# mini_robot.net
KiCad netlist of a schematic drawn in EAGLE
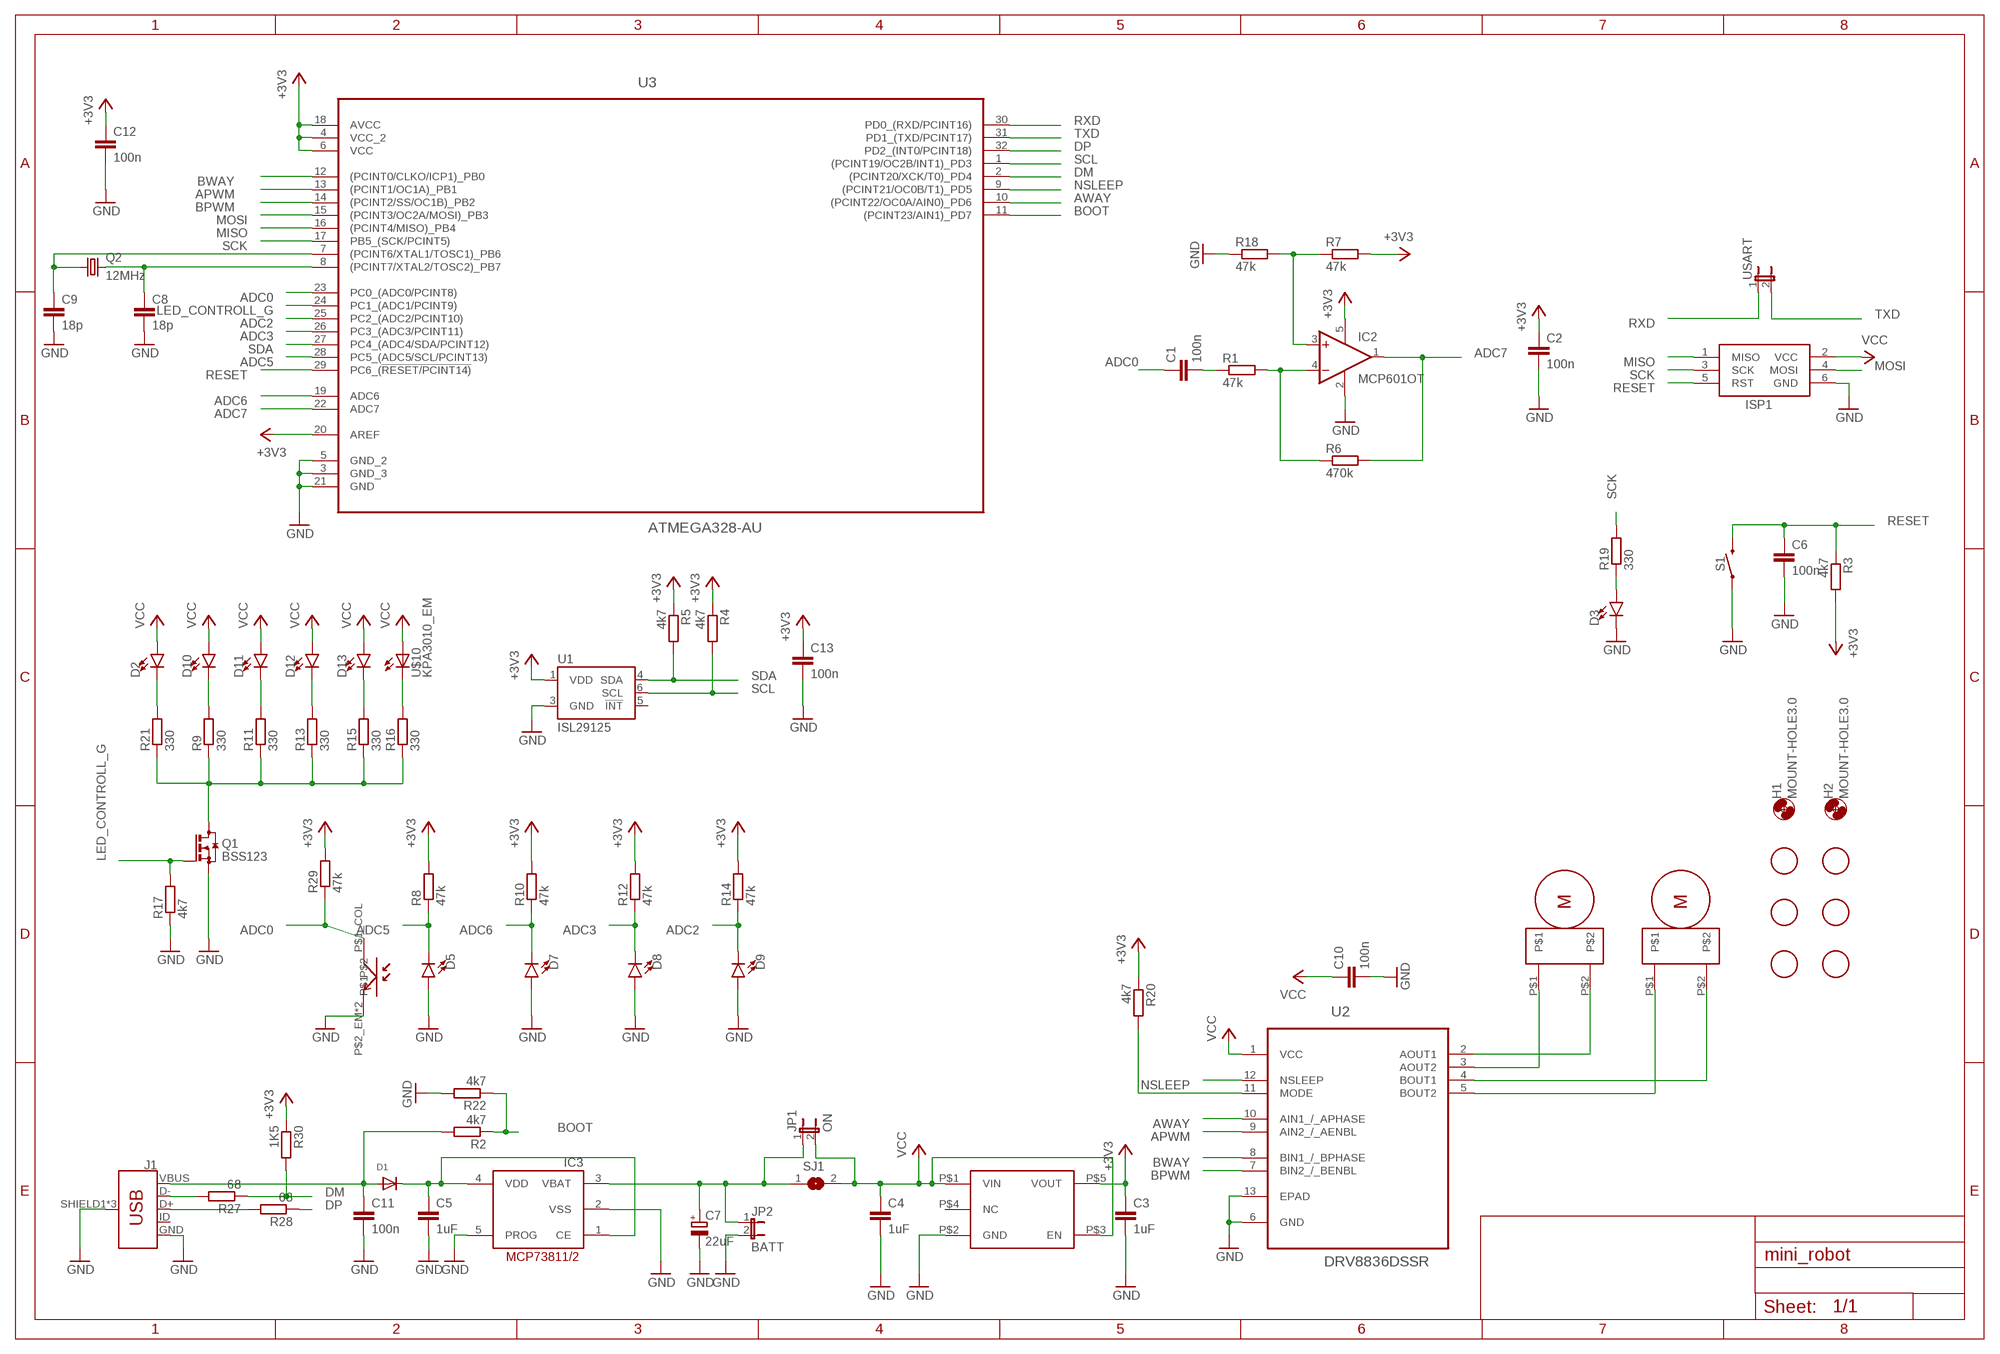
[diagram p0: schematic, sheet 1]

(export (version "E")
  (design (tool "Eeschema 10.0.6"))
  (components
    (comp (ref "C1")
      (value "100n")
      (footprint "eagle-import:C0603")
      (libsource (lib "eagle-import") (part "C-EUC0603"))
    )
    (comp (ref "C2")
      (value "100n")
      (footprint "eagle-import:C0603")
      (libsource (lib "eagle-import") (part "C-EUC0603"))
    )
    (comp (ref "C3")
      (value "1uF")
      (footprint "eagle-import:C0805")
      (libsource (lib "eagle-import") (part "C-EUC0805"))
    )
    (comp (ref "C4")
      (value "1uF")
      (footprint "eagle-import:C0805")
      (libsource (lib "eagle-import") (part "C-EUC0805"))
    )
    (comp (ref "C5")
      (value "1uF")
      (footprint "eagle-import:C0603")
      (libsource (lib "eagle-import") (part "C-EUC0603"))
    )
    (comp (ref "C6")
      (value "100n")
      (footprint "eagle-import:C0603")
      (libsource (lib "eagle-import") (part "C-EUC0603"))
    )
    (comp (ref "C7")
      (value "22uF")
      (footprint "eagle-import:153CLV-0505")
      (libsource (lib "eagle-import") (part "CPOL-EU153CLV-0505"))
    )
    (comp (ref "C8")
      (value "18p")
      (footprint "eagle-import:C0603")
      (libsource (lib "eagle-import") (part "C-EUC0603"))
    )
    (comp (ref "C9")
      (value "18p")
      (footprint "eagle-import:C0603")
      (libsource (lib "eagle-import") (part "C-EUC0603"))
    )
    (comp (ref "C10")
      (value "100n")
      (footprint "eagle-import:C0603")
      (libsource (lib "eagle-import") (part "C-EUC0603"))
    )
    (comp (ref "C11")
      (value "100n")
      (footprint "eagle-import:C0603")
      (libsource (lib "eagle-import") (part "C-EUC0603"))
    )
    (comp (ref "C12")
      (value "100n")
      (footprint "eagle-import:C0603")
      (libsource (lib "eagle-import") (part "C-EUC0603"))
    )
    (comp (ref "C13")
      (value "100n")
      (footprint "eagle-import:C0603")
      (libsource (lib "eagle-import") (part "C-EUC0603"))
    )
    (comp (ref "D1")
      (value "DIODE_SOD-123FL")
      (footprint "eagle-import:SOD-123FL")
      (libsource (lib "eagle-import") (part "DIODE_SOD-123FL"))
    )
    (comp (ref "D2")
      (value "LED-FKIT-1206")
      (footprint "eagle-import:FKIT-LED-1206")
      (libsource (lib "eagle-import") (part "LED-FKIT-1206"))
    )
    (comp (ref "D3")
      (value "LED-FKIT-1206")
      (footprint "eagle-import:FKIT-LED-1206")
      (libsource (lib "eagle-import") (part "LED-FKIT-1206"))
    )
    (comp (ref "D5")
      (value "LED-FKIT-1206")
      (footprint "eagle-import:FKIT-LED-1206")
      (libsource (lib "eagle-import") (part "LED-FKIT-1206"))
    )
    (comp (ref "D7")
      (value "LED-FKIT-1206")
      (footprint "eagle-import:FKIT-LED-1206")
      (libsource (lib "eagle-import") (part "LED-FKIT-1206"))
    )
    (comp (ref "D8")
      (value "LED-FKIT-1206")
      (footprint "eagle-import:FKIT-LED-1206")
      (libsource (lib "eagle-import") (part "LED-FKIT-1206"))
    )
    (comp (ref "D9")
      (value "LED-FKIT-1206")
      (footprint "eagle-import:FKIT-LED-1206")
      (libsource (lib "eagle-import") (part "LED-FKIT-1206"))
    )
    (comp (ref "D10")
      (value "LED-FKIT-1206")
      (footprint "eagle-import:FKIT-LED-1206")
      (libsource (lib "eagle-import") (part "LED-FKIT-1206"))
    )
    (comp (ref "D11")
      (value "LED-FKIT-1206")
      (footprint "eagle-import:FKIT-LED-1206")
      (libsource (lib "eagle-import") (part "LED-FKIT-1206"))
    )
    (comp (ref "D12")
      (value "LED-FKIT-1206")
      (footprint "eagle-import:FKIT-LED-1206")
      (libsource (lib "eagle-import") (part "LED-FKIT-1206"))
    )
    (comp (ref "D13")
      (value "LED-FKIT-1206")
      (footprint "eagle-import:FKIT-LED-1206")
      (libsource (lib "eagle-import") (part "LED-FKIT-1206"))
    )
    (comp (ref "H1")
      (value "MOUNT-HOLE3.0")
      (footprint "eagle-import:3,0")
      (libsource (lib "eagle-import") (part "MOUNT-HOLE3.0"))
    )
    (comp (ref "H2")
      (value "MOUNT-HOLE3.0")
      (footprint "eagle-import:3,0")
      (libsource (lib "eagle-import") (part "MOUNT-HOLE3.0"))
    )
    (comp (ref "IC2")
      (value "MCP601OT")
      (footprint "eagle-import:SOT23-5")
      (libsource (lib "eagle-import") (part "MCP601OT"))
    )
    (comp (ref "IC3")
      (value "MCP73811/2")
      (footprint "eagle-import:SOT23-5L")
      (libsource (lib "eagle-import") (part "MCP73811/2"))
    )
    (comp (ref "ISP1")
      (value "AVRISP-6")
      (footprint "eagle-import:AVRISP")
      (libsource (lib "eagle-import") (part "AVRISP-6"))
    )
    (comp (ref "J1")
      (value "USB_MICRO-B_FEMALE-SMT")
      (footprint "eagle-import:USB-B-MICRO-SMD")
      (libsource (lib "eagle-import") (part "USB_MICRO-B_FEMALE-SMT"))
    )
    (comp (ref "JP1")
      (value "ON")
      (footprint "eagle-import:JP1")
      (libsource (lib "eagle-import") (part "JP1E"))
    )
    (comp (ref "JP2")
      (value "BATT")
      (footprint "eagle-import:JP1")
      (libsource (lib "eagle-import") (part "JP1E"))
    )
    (comp (ref "Q1")
      (value "BSS123")
      (footprint "eagle-import:SOT23")
      (libsource (lib "eagle-import") (part "BSS123"))
    )
    (comp (ref "Q2")
      (value "12MHz")
      (footprint "eagle-import:CTS406")
      (libsource (lib "eagle-import") (part "CRYSTALCTS406"))
    )
    (comp (ref "R1")
      (value "47k")
      (footprint "eagle-import:R0603")
      (libsource (lib "eagle-import") (part "R-EU_R0603"))
    )
    (comp (ref "R2")
      (value "4k7")
      (footprint "eagle-import:R0603")
      (libsource (lib "eagle-import") (part "R-EU_R0603"))
    )
    (comp (ref "R3")
      (value "4k7")
      (footprint "eagle-import:R0603")
      (libsource (lib "eagle-import") (part "R-EU_R0603"))
    )
    (comp (ref "R4")
      (value "4k7")
      (footprint "eagle-import:R0603")
      (libsource (lib "eagle-import") (part "R-EU_R0603"))
    )
    (comp (ref "R5")
      (value "4k7")
      (footprint "eagle-import:R0603")
      (libsource (lib "eagle-import") (part "R-EU_R0603"))
    )
    (comp (ref "R6")
      (value "470k")
      (footprint "eagle-import:R0603")
      (libsource (lib "eagle-import") (part "R-EU_R0603"))
    )
    (comp (ref "R7")
      (value "47k")
      (footprint "eagle-import:R0603")
      (libsource (lib "eagle-import") (part "R-EU_R0603"))
    )
    (comp (ref "R8")
      (value "47k")
      (footprint "eagle-import:R0603")
      (libsource (lib "eagle-import") (part "R-EU_R0603"))
    )
    (comp (ref "R9")
      (value "330")
      (footprint "eagle-import:R0603")
      (libsource (lib "eagle-import") (part "R-EU_R0603"))
    )
    (comp (ref "R10")
      (value "47k")
      (footprint "eagle-import:R0603")
      (libsource (lib "eagle-import") (part "R-EU_R0603"))
    )
    (comp (ref "R11")
      (value "330")
      (footprint "eagle-import:R0603")
      (libsource (lib "eagle-import") (part "R-EU_R0603"))
    )
    (comp (ref "R12")
      (value "47k")
      (footprint "eagle-import:R0603")
      (libsource (lib "eagle-import") (part "R-EU_R0603"))
    )
    (comp (ref "R13")
      (value "330")
      (footprint "eagle-import:R0603")
      (libsource (lib "eagle-import") (part "R-EU_R0603"))
    )
    (comp (ref "R14")
      (value "47k")
      (footprint "eagle-import:R0603")
      (libsource (lib "eagle-import") (part "R-EU_R0603"))
    )
    (comp (ref "R15")
      (value "330")
      (footprint "eagle-import:R0603")
      (libsource (lib "eagle-import") (part "R-EU_R0603"))
    )
    (comp (ref "R16")
      (value "330")
      (footprint "eagle-import:R0603")
      (libsource (lib "eagle-import") (part "R-EU_R0603"))
    )
    (comp (ref "R17")
      (value "4k7")
      (footprint "eagle-import:R0603")
      (libsource (lib "eagle-import") (part "R-EU_R0603"))
    )
    (comp (ref "R18")
      (value "47k")
      (footprint "eagle-import:R0603")
      (libsource (lib "eagle-import") (part "R-EU_R0603"))
    )
    (comp (ref "R19")
      (value "330")
      (footprint "eagle-import:R0603")
      (libsource (lib "eagle-import") (part "R-EU_R0603"))
    )
    (comp (ref "R20")
      (value "4k7")
      (footprint "eagle-import:R0603")
      (libsource (lib "eagle-import") (part "R-EU_R0603"))
    )
    (comp (ref "R21")
      (value "330")
      (footprint "eagle-import:R0603")
      (libsource (lib "eagle-import") (part "R-EU_R0603"))
    )
    (comp (ref "R22")
      (value "4k7")
      (footprint "eagle-import:R0603")
      (libsource (lib "eagle-import") (part "R-EU_R0603"))
    )
    (comp (ref "R27")
      (value "68")
      (footprint "eagle-import:R0603")
      (libsource (lib "eagle-import") (part "R-EU_R0603"))
    )
    (comp (ref "R28")
      (value "68")
      (footprint "eagle-import:R0603")
      (libsource (lib "eagle-import") (part "R-EU_R0603"))
    )
    (comp (ref "R29")
      (value "47k")
      (footprint "eagle-import:R0603")
      (libsource (lib "eagle-import") (part "R-EU_R0603"))
    )
    (comp (ref "R30")
      (value "1K5")
      (footprint "eagle-import:R0603")
      (libsource (lib "eagle-import") (part "R-EU_R0603"))
    )
    (comp (ref "S1")
      (value "MOMENTARY-SWITCH-SPST-SMD-6.2MM-TALL")
      (footprint "eagle-import:TACTILE_SWITCH_SMD_6.2MM_TALL")
      (libsource (lib "eagle-import") (part "MOMENTARY-SWITCH-SPST-SMD-6.2MM-TALL"))
    )
    (comp (ref "SJ1") (value "SJ") (footprint "eagle-import:SJ") (libsource (lib "eagle-import") (part "SJ")))
    (comp (ref "U$1")
      (value "FIDUCIAL")
      (footprint "eagle-import:FIDUCIAL_1MM")
      (libsource (lib "eagle-import") (part "FIDUCIAL"))
    )
    (comp (ref "U$2")
      (value "KPA3010")
      (footprint "eagle-import:KPA3010")
      (libsource (lib "eagle-import") (part "KPA3010"))
    )
    (comp (ref "U$3")
      (value "FIDUCIAL")
      (footprint "eagle-import:FIDUCIAL_1MM")
      (libsource (lib "eagle-import") (part "FIDUCIAL"))
    )
    (comp (ref "U$4")
      (value "FIDUCIAL")
      (footprint "eagle-import:FIDUCIAL_1MM")
      (libsource (lib "eagle-import") (part "FIDUCIAL"))
    )
    (comp (ref "U$5")
      (value "FIDUCIAL")
      (footprint "eagle-import:FIDUCIAL_1MM")
      (libsource (lib "eagle-import") (part "FIDUCIAL"))
    )
    (comp (ref "U$6")
      (value "FIDUCIAL")
      (footprint "eagle-import:FIDUCIAL_1MM")
      (libsource (lib "eagle-import") (part "FIDUCIAL"))
    )
    (comp (ref "U$7")
      (value "FIDUCIAL")
      (footprint "eagle-import:FIDUCIAL_1MM")
      (libsource (lib "eagle-import") (part "FIDUCIAL"))
    )
    (comp (ref "U$8")
      (value "PLANETARY_GEAR_MOTOR")
      (footprint "eagle-import:PLANETARY_GEAR_MOTOR")
      (libsource (lib "eagle-import") (part "PLANETARY_GEAR_MOTOR"))
    )
    (comp (ref "U$9")
      (value "PLANETARY_GEAR_MOTOR")
      (footprint "eagle-import:PLANETARY_GEAR_MOTOR")
      (libsource (lib "eagle-import") (part "PLANETARY_GEAR_MOTOR"))
    )
    (comp (ref "U$10")
      (value "KPA3010_EM")
      (footprint "eagle-import:KPA3010")
      (libsource (lib "eagle-import") (part "KPA3010_EM"))
    )
    (comp (ref "U$11")
      (value "MIC5504-3.3Y")
      (footprint "eagle-import:SOT23-5")
      (libsource (lib "eagle-import") (part "MIC5504-3.3Y"))
    )
    (comp (ref "U1")
      (value "ISL29125")
      (footprint "eagle-import:ODFN-LD-6")
      (libsource (lib "eagle-import") (part "ISL29125"))
    )
    (comp (ref "U2")
      (value "DRV8836DSSR")
      (footprint "eagle-import:SON50P200X300X80-13N")
      (fields (field (name "MPN") "DRV8836DSSR "))
      (libsource (lib "eagle-import") (part "DRV8836DSSR"))
    )
    (comp (ref "U3")
      (value "ATMEGA328-AU")
      (footprint "eagle-import:QFP80P900X900X120-32N")
      (libsource (lib "eagle-import") (part "ATMEGA328-AU"))
    )
    (comp (ref "USART")
      (value "JP1E")
      (footprint "eagle-import:JP1")
      (libsource (lib "eagle-import") (part "JP1E"))
    )
  )
  (nets
    (net (code "1") (name "+3V3") (class "Default")
      (node (ref "C12") (pin "1") (pinfunction "1_1") (pintype "passive"))
      (node (ref "C13") (pin "1") (pinfunction "1_1") (pintype "passive"))
      (node (ref "C2") (pin "1") (pinfunction "1_1") (pintype "passive"))
      (node (ref "C3") (pin "1") (pinfunction "1_1") (pintype "passive"))
      (node (ref "IC2") (pin "5") (pinfunction "V+_5") (pintype "power_in"))
      (node (ref "R10") (pin "2") (pinfunction "2_2") (pintype "passive"))
      (node (ref "R12") (pin "2") (pinfunction "2_2") (pintype "passive"))
      (node (ref "R14") (pin "2") (pinfunction "2_2") (pintype "passive"))
      (node (ref "R20") (pin "1") (pinfunction "1_1") (pintype "passive"))
      (node (ref "R29") (pin "2") (pinfunction "2_2") (pintype "passive"))
      (node (ref "R3") (pin "2") (pinfunction "2_2") (pintype "passive"))
      (node (ref "R30") (pin "1") (pinfunction "1_1") (pintype "passive"))
      (node (ref "R4") (pin "1") (pinfunction "1_1") (pintype "passive"))
      (node (ref "R5") (pin "1") (pinfunction "1_1") (pintype "passive"))
      (node (ref "R7") (pin "2") (pinfunction "2_2") (pintype "passive"))
      (node (ref "R8") (pin "2") (pinfunction "2_2") (pintype "passive"))
      (node (ref "U$11") (pin "P$5") (pinfunction "VOUT_P$5") (pintype "bidirectional"))
      (node (ref "U1") (pin "1") (pinfunction "VDD_1") (pintype "bidirectional"))
      (node (ref "U3") (pin "18") (pinfunction "AVCC_18") (pintype "power_in"))
      (node (ref "U3") (pin "20") (pinfunction "AREF_20") (pintype "passive"))
      (node (ref "U3") (pin "4") (pinfunction "VCC_2_4") (pintype "power_in"))
      (node (ref "U3") (pin "6") (pinfunction "VCC_6") (pintype "power_in"))
    )
    (net (code "2") (name "/ADC0") (class "Default")
      (node (ref "C1") (pin "1") (pinfunction "1_1") (pintype "passive"))
      (node (ref "R29") (pin "1") (pinfunction "1_1") (pintype "passive"))
      (node (ref "U$2") (pin "P$1_COL") (pinfunction "P$1_P$1_COL") (pintype "bidirectional"))
      (node (ref "U3") (pin "23") (pinfunction "PC0_(ADC0/PCINT8)_23") (pintype "bidirectional"))
    )
    (net (code "3") (name "/ADC2") (class "Default")
      (node (ref "D9") (pin "C") (pinfunction "C_C") (pintype "passive"))
      (node (ref "R14") (pin "1") (pinfunction "1_1") (pintype "passive"))
      (node (ref "U3") (pin "25") (pinfunction "PC2_(ADC2/PCINT10)_25") (pintype "bidirectional"))
    )
    (net (code "4") (name "/ADC3") (class "Default")
      (node (ref "D8") (pin "C") (pinfunction "C_C") (pintype "passive"))
      (node (ref "R12") (pin "1") (pinfunction "1_1") (pintype "passive"))
      (node (ref "U3") (pin "26") (pinfunction "PC3_(ADC3/PCINT11)_26") (pintype "bidirectional"))
    )
    (net (code "5") (name "/ADC5") (class "Default")
      (node (ref "D5") (pin "C") (pinfunction "C_C") (pintype "passive"))
      (node (ref "R8") (pin "1") (pinfunction "1_1") (pintype "passive"))
      (node (ref "U3") (pin "28") (pinfunction "PC5_(ADC5/SCL/PCINT13)_28") (pintype "bidirectional"))
    )
    (net (code "6") (name "/ADC6") (class "Default")
      (node (ref "D7") (pin "C") (pinfunction "C_C") (pintype "passive"))
      (node (ref "R10") (pin "1") (pinfunction "1_1") (pintype "passive"))
      (node (ref "U3") (pin "19") (pinfunction "ADC6_19") (pintype "input"))
    )
    (net (code "7") (name "/ADC7") (class "Default")
      (node (ref "IC2") (pin "1") (pinfunction "OUT_1") (pintype "output"))
      (node (ref "R6") (pin "2") (pinfunction "2_2") (pintype "passive"))
      (node (ref "U3") (pin "22") (pinfunction "ADC7_22") (pintype "input"))
    )
    (net (code "8") (name "/APWM") (class "Default")
      (node (ref "U2") (pin "9") (pinfunction "AIN2_/_AENBL_9") (pintype "input"))
      (node (ref "U3") (pin "13") (pinfunction "(PCINT1/OC1A)_PB1_13") (pintype "bidirectional"))
    )
    (net (code "9") (name "/AWAY") (class "Default")
      (node (ref "U2") (pin "10") (pinfunction "AIN1_/_APHASE_10") (pintype "input"))
      (node (ref "U3") (pin "10") (pinfunction "(PCINT22/OC0A/AIN0)_PD6_10") (pintype "bidirectional"))
    )
    (net (code "10") (name "/BOOT") (class "Default")
      (node (ref "R2") (pin "1") (pinfunction "1_1") (pintype "passive"))
      (node (ref "R22") (pin "1") (pinfunction "1_1") (pintype "passive"))
      (node (ref "U3") (pin "11") (pinfunction "(PCINT23/AIN1)_PD7_11") (pintype "bidirectional"))
    )
    (net (code "11") (name "/BPWM") (class "Default")
      (node (ref "U2") (pin "7") (pinfunction "BIN2_/_BENBL_7") (pintype "input"))
      (node (ref "U3") (pin "14") (pinfunction "(PCINT2/SS/OC1B)_PB2_14") (pintype "bidirectional"))
    )
    (net (code "12") (name "/BWAY") (class "Default")
      (node (ref "U2") (pin "8") (pinfunction "BIN1_/_BPHASE_8") (pintype "input"))
      (node (ref "U3") (pin "12") (pinfunction "(PCINT0/CLKO/ICP1)_PB0_12") (pintype "bidirectional"))
    )
    (net (code "13") (name "/DM") (class "Default")
      (node (ref "R27") (pin "1") (pinfunction "1_1") (pintype "passive"))
      (node (ref "R30") (pin "2") (pinfunction "2_2") (pintype "passive"))
      (node (ref "U3") (pin "2") (pinfunction "(PCINT20/XCK/T0)_PD4_2") (pintype "bidirectional"))
    )
    (net (code "14") (name "/DP") (class "Default")
      (node (ref "R28") (pin "1") (pinfunction "1_1") (pintype "passive"))
      (node (ref "U3") (pin "32") (pinfunction "PD2_(INT0/PCINT18)_32") (pintype "bidirectional"))
    )
    (net (code "15") (name "/LED_CONTROLL_G") (class "Default")
      (node (ref "Q1") (pin "1") (pinfunction "G_1") (pintype "passive"))
      (node (ref "R17") (pin "2") (pinfunction "2_2") (pintype "passive"))
      (node (ref "U3") (pin "24") (pinfunction "PC1_(ADC1/PCINT9)_24") (pintype "bidirectional"))
    )
    (net (code "16") (name "/MISO") (class "Default")
      (node (ref "ISP1") (pin "1") (pinfunction "MISO_1") (pintype "input"))
      (node (ref "U3") (pin "16") (pinfunction "(PCINT4/MISO)_PB4_16") (pintype "bidirectional"))
    )
    (net (code "17") (name "/MOSI") (class "Default")
      (node (ref "ISP1") (pin "4") (pinfunction "MOSI_4") (pintype "output"))
      (node (ref "U3") (pin "15") (pinfunction "(PCINT3/OC2A/MOSI)_PB3_15") (pintype "bidirectional"))
    )
    (net (code "18") (name "/NSLEEP") (class "Default")
      (node (ref "U2") (pin "12") (pinfunction "NSLEEP_12") (pintype "input"))
      (node (ref "U3") (pin "9") (pinfunction "(PCINT21/OC0B/T1)_PD5_9") (pintype "bidirectional"))
    )
    (net (code "19") (name "/RESET") (class "Default")
      (node (ref "C6") (pin "1") (pinfunction "1_1") (pintype "passive"))
      (node (ref "ISP1") (pin "5") (pinfunction "RST_5") (pintype "output"))
      (node (ref "R3") (pin "1") (pinfunction "1_1") (pintype "passive"))
      (node (ref "S1") (pin "B2") (pinfunction "2_B2") (pintype "passive"))
      (node (ref "U3") (pin "29") (pinfunction "PC6_(~{RESET/PCINT14})_29") (pintype "bidirectional"))
    )
    (net (code "20") (name "/RXD") (class "Default")
      (node (ref "U3") (pin "30") (pinfunction "PD0_(RXD/PCINT16)_30") (pintype "bidirectional"))
      (node (ref "USART") (pin "1") (pinfunction "1_1") (pintype "passive"))
    )
    (net (code "21") (name "/SCK") (class "Default")
      (node (ref "ISP1") (pin "3") (pinfunction "SCK_3") (pintype "output"))
      (node (ref "R19") (pin "2") (pinfunction "2_2") (pintype "passive"))
      (node (ref "U3") (pin "17") (pinfunction "PB5_(SCK/PCINT5)_17") (pintype "bidirectional"))
    )
    (net (code "22") (name "/SCL") (class "Default")
      (node (ref "R4") (pin "2") (pinfunction "2_2") (pintype "passive"))
      (node (ref "U1") (pin "6") (pinfunction "SCL_6") (pintype "bidirectional"))
      (node (ref "U3") (pin "1") (pinfunction "(PCINT19/OC2B/INT1)_PD3_1") (pintype "bidirectional"))
    )
    (net (code "23") (name "/SDA") (class "Default")
      (node (ref "R5") (pin "2") (pinfunction "2_2") (pintype "passive"))
      (node (ref "U1") (pin "4") (pinfunction "SDA_4") (pintype "bidirectional"))
      (node (ref "U3") (pin "27") (pinfunction "PC4_(ADC4/SDA/PCINT12)_27") (pintype "bidirectional"))
    )
    (net (code "24") (name "/TXD") (class "Default")
      (node (ref "U3") (pin "31") (pinfunction "PD1_(TXD/PCINT17)_31") (pintype "bidirectional"))
      (node (ref "USART") (pin "2") (pinfunction "2_2") (pintype "passive"))
    )
    (net (code "25") (name "GND") (class "Default")
      (node (ref "C10") (pin "2") (pinfunction "2_2") (pintype "passive"))
      (node (ref "C11") (pin "2") (pinfunction "2_2") (pintype "passive"))
      (node (ref "C12") (pin "2") (pinfunction "2_2") (pintype "passive"))
      (node (ref "C13") (pin "2") (pinfunction "2_2") (pintype "passive"))
      (node (ref "C2") (pin "2") (pinfunction "2_2") (pintype "passive"))
      (node (ref "C3") (pin "2") (pinfunction "2_2") (pintype "passive"))
      (node (ref "C4") (pin "2") (pinfunction "2_2") (pintype "passive"))
      (node (ref "C5") (pin "2") (pinfunction "2_2") (pintype "passive"))
      (node (ref "C6") (pin "2") (pinfunction "2_2") (pintype "passive"))
      (node (ref "C7") (pin "-") (pinfunction "-_-") (pintype "passive"))
      (node (ref "C8") (pin "2") (pinfunction "2_2") (pintype "passive"))
      (node (ref "C9") (pin "2") (pinfunction "2_2") (pintype "passive"))
      (node (ref "D3") (pin "C") (pinfunction "C_C") (pintype "passive"))
      (node (ref "D5") (pin "A") (pinfunction "A_A") (pintype "passive"))
      (node (ref "D7") (pin "A") (pinfunction "A_A") (pintype "passive"))
      (node (ref "D8") (pin "A") (pinfunction "A_A") (pintype "passive"))
      (node (ref "D9") (pin "A") (pinfunction "A_A") (pintype "passive"))
      (node (ref "IC2") (pin "2") (pinfunction "V-_2") (pintype "power_in"))
      (node (ref "IC3") (pin "2") (pinfunction "VSS_2") (pintype "power_in"))
      (node (ref "IC3") (pin "5") (pinfunction "PROG_5") (pintype "input"))
      (node (ref "ISP1") (pin "6") (pinfunction "GND_6") (pintype "power_in"))
      (node (ref "J1") (pin "GND") (pinfunction "GND_GND") (pintype "power_in"))
      (node (ref "J1") (pin "SHIELD1") (pinfunction "SHIELD_SHIELD1") (pintype "bidirectional"))
      (node (ref "J1") (pin "SHIELD2") (pinfunction "SHIELD_SHIELD2") (pintype "bidirectional"))
      (node (ref "J1") (pin "SHIELD3") (pinfunction "SHIELD_SHIELD3") (pintype "bidirectional"))
      (node (ref "JP2") (pin "2") (pinfunction "2_2") (pintype "passive"))
      (node (ref "Q1") (pin "2") (pinfunction "S_2") (pintype "passive"))
      (node (ref "R17") (pin "1") (pinfunction "1_1") (pintype "passive"))
      (node (ref "R18") (pin "1") (pinfunction "1_1") (pintype "passive"))
      (node (ref "R22") (pin "2") (pinfunction "2_2") (pintype "passive"))
      (node (ref "S1") (pin "A2") (pinfunction "1_A2") (pintype "passive"))
      (node (ref "U$11") (pin "P$2") (pinfunction "GND_P$2") (pintype "bidirectional"))
      (node (ref "U$2") (pin "P$2_EM") (pinfunction "P$2_P$2_EM") (pintype "bidirectional"))
      (node (ref "U$2") (pin "P$3-NC") (pinfunction "P$2_P$3-NC") (pintype "bidirectional"))
      (node (ref "U1") (pin "3") (pinfunction "GND_3") (pintype "bidirectional"))
      (node (ref "U2") (pin "13") (pinfunction "EPAD_13") (pintype "passive"))
      (node (ref "U2") (pin "6") (pinfunction "GND_6") (pintype "passive"))
      (node (ref "U3") (pin "21") (pinfunction "GND_21") (pintype "passive"))
      (node (ref "U3") (pin "3") (pinfunction "GND_3_3") (pintype "passive"))
      (node (ref "U3") (pin "5") (pinfunction "GND_2_5") (pintype "passive"))
    )
    (net (code "26") (name "Net-(C1-Pad2)") (class "Default")
      (node (ref "C1") (pin "2") (pinfunction "2_2") (pintype "passive"))
      (node (ref "R1") (pin "1") (pinfunction "1_1") (pintype "passive"))
    )
    (net (code "27") (name "Net-(C11-Pad1)") (class "Default")
      (node (ref "C11") (pin "1") (pinfunction "1_1") (pintype "passive"))
      (node (ref "D1") (pin "A") (pinfunction "A_A") (pintype "passive"))
      (node (ref "J1") (pin "VBUS") (pinfunction "VBUS_VBUS") (pintype "power_in"))
      (node (ref "R2") (pin "2") (pinfunction "2_2") (pintype "passive"))
    )
    (net (code "28") (name "Net-(D2-PadC)") (class "Default")
      (node (ref "D2") (pin "C") (pinfunction "C_C") (pintype "passive"))
      (node (ref "R21") (pin "2") (pinfunction "2_2") (pintype "passive"))
    )
    (net (code "29") (name "Net-(D3-PadA)") (class "Default")
      (node (ref "D3") (pin "A") (pinfunction "A_A") (pintype "passive"))
      (node (ref "R19") (pin "1") (pinfunction "1_1") (pintype "passive"))
    )
    (net (code "30") (name "Net-(D10-PadC)") (class "Default")
      (node (ref "D10") (pin "C") (pinfunction "C_C") (pintype "passive"))
      (node (ref "R9") (pin "2") (pinfunction "2_2") (pintype "passive"))
    )
    (net (code "31") (name "Net-(D11-PadC)") (class "Default")
      (node (ref "D11") (pin "C") (pinfunction "C_C") (pintype "passive"))
      (node (ref "R11") (pin "2") (pinfunction "2_2") (pintype "passive"))
    )
    (net (code "32") (name "Net-(D12-PadC)") (class "Default")
      (node (ref "D12") (pin "C") (pinfunction "C_C") (pintype "passive"))
      (node (ref "R13") (pin "2") (pinfunction "2_2") (pintype "passive"))
    )
    (net (code "33") (name "Net-(D13-PadC)") (class "Default")
      (node (ref "D13") (pin "C") (pinfunction "C_C") (pintype "passive"))
      (node (ref "R15") (pin "2") (pinfunction "2_2") (pintype "passive"))
    )
    (net (code "34") (name "Net-(IC2-+IN)") (class "Default")
      (node (ref "IC2") (pin "3") (pinfunction "+IN_3") (pintype "input"))
      (node (ref "R18") (pin "2") (pinfunction "2_2") (pintype "passive"))
      (node (ref "R7") (pin "1") (pinfunction "1_1") (pintype "passive"))
    )
    (net (code "35") (name "Net-(IC2--IN)") (class "Default")
      (node (ref "IC2") (pin "4") (pinfunction "-IN_4") (pintype "input"))
      (node (ref "R1") (pin "2") (pinfunction "2_2") (pintype "passive"))
      (node (ref "R6") (pin "1") (pinfunction "1_1") (pintype "passive"))
    )
    (net (code "36") (name "Net-(IC3-CE)") (class "Default")
      (node (ref "C5") (pin "1") (pinfunction "1_1") (pintype "passive"))
      (node (ref "D1") (pin "C") (pinfunction "C_C") (pintype "passive"))
      (node (ref "IC3") (pin "1") (pinfunction "CE_1") (pintype "input"))
      (node (ref "IC3") (pin "4") (pinfunction "VDD_4") (pintype "power_in"))
    )
    (net (code "37") (name "Net-(IC3-VBAT)") (class "Default")
      (node (ref "C7") (pin "+") (pinfunction "+_+") (pintype "passive"))
      (node (ref "IC3") (pin "3") (pinfunction "VBAT_3") (pintype "bidirectional"))
      (node (ref "JP1") (pin "1") (pinfunction "1_1") (pintype "passive"))
      (node (ref "JP2") (pin "1") (pinfunction "1_1") (pintype "passive"))
      (node (ref "SJ1") (pin "1") (pinfunction "1_1") (pintype "passive"))
    )
    (net (code "38") (name "Net-(J1-PadD+)") (class "Default")
      (node (ref "J1") (pin "D+") (pinfunction "D+_D+") (pintype "bidirectional"))
      (node (ref "R28") (pin "2") (pinfunction "2_2") (pintype "passive"))
    )
    (net (code "39") (name "Net-(J1-PadD-)") (class "Default")
      (node (ref "J1") (pin "D-") (pinfunction "D-_D-") (pintype "bidirectional"))
      (node (ref "R27") (pin "2") (pinfunction "2_2") (pintype "passive"))
    )
    (net (code "40") (name "Net-(Q1-D)") (class "Default")
      (node (ref "Q1") (pin "3") (pinfunction "D_3") (pintype "passive"))
      (node (ref "R11") (pin "1") (pinfunction "1_1") (pintype "passive"))
      (node (ref "R13") (pin "1") (pinfunction "1_1") (pintype "passive"))
      (node (ref "R15") (pin "1") (pinfunction "1_1") (pintype "passive"))
      (node (ref "R16") (pin "1") (pinfunction "1_1") (pintype "passive"))
      (node (ref "R21") (pin "1") (pinfunction "1_1") (pintype "passive"))
      (node (ref "R9") (pin "1") (pinfunction "1_1") (pintype "passive"))
    )
    (net (code "41") (name "Net-(Q2-2)") (class "Default")
      (node (ref "C8") (pin "1") (pinfunction "1_1") (pintype "passive"))
      (node (ref "Q2") (pin "3") (pinfunction "2_3") (pintype "passive"))
      (node (ref "U3") (pin "8") (pinfunction "(PCINT7/XTAL2/TOSC2)_PB7_8") (pintype "bidirectional"))
    )
    (net (code "42") (name "Net-(U$10-C)") (class "Default")
      (node (ref "R16") (pin "2") (pinfunction "2_2") (pintype "passive"))
      (node (ref "U$10") (pin "P$1_COL") (pinfunction "C_P$1_COL") (pintype "passive"))
    )
    (net (code "43") (name "Net-(U2-AOUT1)") (class "Default")
      (node (ref "U$8") (pin "P$2") (pinfunction "P$2_P$2") (pintype "bidirectional"))
      (node (ref "U2") (pin "2") (pinfunction "AOUT1_2") (pintype "output"))
    )
    (net (code "44") (name "Net-(U2-AOUT2)") (class "Default")
      (node (ref "U$8") (pin "P$1") (pinfunction "P$1_P$1") (pintype "bidirectional"))
      (node (ref "U2") (pin "3") (pinfunction "AOUT2_3") (pintype "output"))
    )
    (net (code "45") (name "Net-(U2-BOUT1)") (class "Default")
      (node (ref "U$9") (pin "P$2") (pinfunction "P$2_P$2") (pintype "bidirectional"))
      (node (ref "U2") (pin "4") (pinfunction "BOUT1_4") (pintype "output"))
    )
    (net (code "46") (name "Net-(U2-BOUT2)") (class "Default")
      (node (ref "U$9") (pin "P$1") (pinfunction "P$1_P$1") (pintype "bidirectional"))
      (node (ref "U2") (pin "5") (pinfunction "BOUT2_5") (pintype "output"))
    )
    (net (code "47") (name "Net-(U2-MODE)") (class "Default")
      (node (ref "R20") (pin "2") (pinfunction "2_2") (pintype "passive"))
      (node (ref "U2") (pin "11") (pinfunction "MODE_11") (pintype "input"))
    )
    (net (code "48") (name "Net-(U3-(PCINT6{slash}XTAL1{slash}TOSC1)_PB6)") (class "Default")
      (node (ref "C9") (pin "1") (pinfunction "1_1") (pintype "passive"))
      (node (ref "Q2") (pin "1") (pinfunction "1_1") (pintype "passive"))
      (node (ref "U3") (pin "7") (pinfunction "(PCINT6/XTAL1/TOSC1)_PB6_7") (pintype "bidirectional"))
    )
    (net (code "49") (name "VCC") (class "Default")
      (node (ref "C10") (pin "1") (pinfunction "1_1") (pintype "passive"))
      (node (ref "C4") (pin "1") (pinfunction "1_1") (pintype "passive"))
      (node (ref "D10") (pin "A") (pinfunction "A_A") (pintype "passive"))
      (node (ref "D11") (pin "A") (pinfunction "A_A") (pintype "passive"))
      (node (ref "D12") (pin "A") (pinfunction "A_A") (pintype "passive"))
      (node (ref "D13") (pin "A") (pinfunction "A_A") (pintype "passive"))
      (node (ref "D2") (pin "A") (pinfunction "A_A") (pintype "passive"))
      (node (ref "ISP1") (pin "2") (pinfunction "VCC_2") (pintype "power_in"))
      (node (ref "JP1") (pin "2") (pinfunction "2_2") (pintype "passive"))
      (node (ref "SJ1") (pin "2") (pinfunction "2_2") (pintype "passive"))
      (node (ref "U$10") (pin "P$2_EM") (pinfunction "A_P$2_EM") (pintype "passive"))
      (node (ref "U$10") (pin "P$3-NC") (pinfunction "A_P$3-NC") (pintype "passive"))
      (node (ref "U$11") (pin "P$1") (pinfunction "VIN_P$1") (pintype "bidirectional"))
      (node (ref "U$11") (pin "P$3") (pinfunction "EN_P$3") (pintype "bidirectional"))
      (node (ref "U2") (pin "1") (pinfunction "VCC_1") (pintype "power_in"))
    )
    (net (code "50") (name "unconnected-(J1-PadID)") (class "Default")
      (node (ref "J1") (pin "ID") (pinfunction "ID_ID") (pintype "bidirectional"))
    )
    (net (code "51") (name "unconnected-(U$11-NC-PadP$4)") (class "Default")
      (node (ref "U$11") (pin "P$4") (pinfunction "NC_P$4") (pintype "bidirectional"))
    )
    (net (code "52") (name "unconnected-(U1-~{INT}-Pad5)") (class "Default")
      (node (ref "U1") (pin "5") (pinfunction "~{INT}_5") (pintype "bidirectional"))
    )
  )
)
